# rs232_conn.net
KiCad netlist of a schematic drawn in Altium Designer
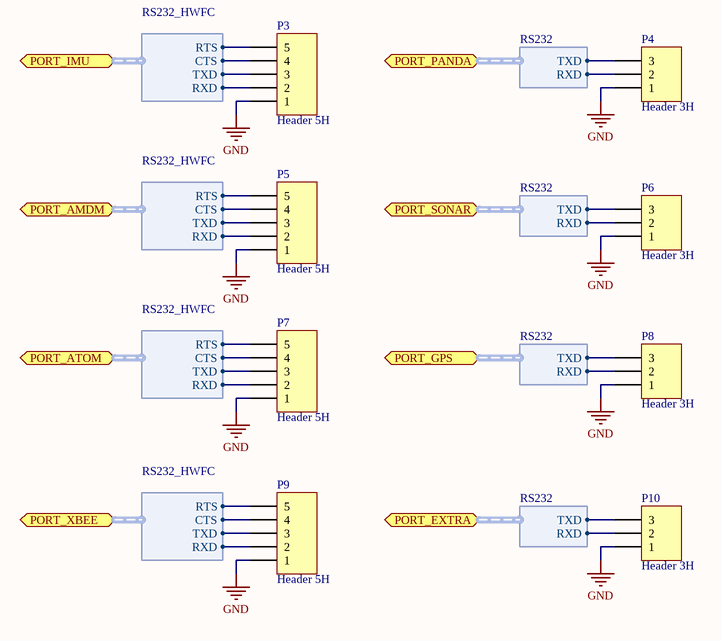
[diagram p0: rs232_conn.SchDoc]

(export (version "E")
  (design (tool "Eeschema 10.0.6"))
  (components
    (comp (ref "P3")
      (value "Header 5H")
      (footprint "S05B-PASK-2")
      (description "Header, 5-Pin, Right Angle")
      (fields (field (name "PUBLISHER") "Altium Limited"))
      (libsource (lib "Miscellaneous Connectors") (part "Header 5H"))
    )
    (comp (ref "P4")
      (value "Header 3H")
      (footprint "S03B-PASK-2")
      (description "Header, 3-Pin, Right Angle")
      (fields (field (name "PUBLISHER") "Altium Limited"))
      (libsource (lib "Miscellaneous Connectors") (part "Header 3H"))
    )
    (comp (ref "P5")
      (value "Header 5H")
      (footprint "S05B-PASK-2")
      (description "Header, 5-Pin, Right Angle")
      (fields (field (name "PUBLISHER") "Altium Limited"))
      (libsource (lib "Miscellaneous Connectors") (part "Header 5H"))
    )
    (comp (ref "P6")
      (value "Header 3H")
      (footprint "S03B-PASK-2")
      (description "Header, 3-Pin, Right Angle")
      (fields (field (name "PUBLISHER") "Altium Limited"))
      (libsource (lib "Miscellaneous Connectors") (part "Header 3H"))
    )
    (comp (ref "P7")
      (value "Header 5H")
      (footprint "S05B-PASK-2")
      (description "Header, 5-Pin, Right Angle")
      (fields (field (name "PUBLISHER") "Altium Limited"))
      (libsource (lib "Miscellaneous Connectors") (part "Header 5H"))
    )
    (comp (ref "P8")
      (value "Header 3H")
      (footprint "S03B-PASK-2")
      (description "Header, 3-Pin, Right Angle")
      (fields (field (name "PUBLISHER") "Altium Limited"))
      (libsource (lib "Miscellaneous Connectors") (part "Header 3H"))
    )
    (comp (ref "P9")
      (value "Header 5H")
      (footprint "S05B-PASK-2")
      (description "Header, 5-Pin, Right Angle")
      (fields (field (name "PUBLISHER") "Altium Limited"))
      (libsource (lib "Miscellaneous Connectors") (part "Header 5H"))
    )
    (comp (ref "P10")
      (value "Header 3H")
      (footprint "S03B-PASK-2")
      (description "Header, 3-Pin, Right Angle")
      (fields (field (name "PUBLISHER") "Altium Limited"))
      (libsource (lib "Miscellaneous Connectors") (part "Header 3H"))
    )
  )
  (nets
    (net (code "5") (name "GND") (class "Default")
      (node (ref "P10") (pin "1") (pinfunction "1_1") (pintype "passive"))
      (node (ref "P3") (pin "1") (pinfunction "1_1") (pintype "passive"))
      (node (ref "P4") (pin "1") (pinfunction "1_1") (pintype "passive"))
      (node (ref "P5") (pin "1") (pinfunction "1_1") (pintype "passive"))
      (node (ref "P6") (pin "1") (pinfunction "1_1") (pintype "passive"))
      (node (ref "P7") (pin "1") (pinfunction "1_1") (pintype "passive"))
      (node (ref "P8") (pin "1") (pinfunction "1_1") (pintype "passive"))
      (node (ref "P9") (pin "1") (pinfunction "1_1") (pintype "passive"))
    )
    (net (code "6") (name "unconnected-(P3-Pad2)") (class "Default")
      (node (ref "P3") (pin "2") (pinfunction "2_2") (pintype "passive"))
    )
    (net (code "7") (name "unconnected-(P3-Pad3)") (class "Default")
      (node (ref "P3") (pin "3") (pinfunction "3_3") (pintype "passive"))
    )
    (net (code "8") (name "unconnected-(P3-Pad4)") (class "Default")
      (node (ref "P3") (pin "4") (pinfunction "4_4") (pintype "passive"))
    )
    (net (code "9") (name "unconnected-(P3-Pad5)") (class "Default")
      (node (ref "P3") (pin "5") (pinfunction "5_5") (pintype "passive"))
    )
    (net (code "10") (name "unconnected-(P4-Pad2)") (class "Default")
      (node (ref "P4") (pin "2") (pinfunction "2_2") (pintype "passive"))
    )
    (net (code "11") (name "unconnected-(P4-Pad3)") (class "Default")
      (node (ref "P4") (pin "3") (pinfunction "3_3") (pintype "passive"))
    )
    (net (code "12") (name "unconnected-(P5-Pad2)") (class "Default")
      (node (ref "P5") (pin "2") (pinfunction "2_2") (pintype "passive"))
    )
    (net (code "13") (name "unconnected-(P5-Pad3)") (class "Default")
      (node (ref "P5") (pin "3") (pinfunction "3_3") (pintype "passive"))
    )
    (net (code "14") (name "unconnected-(P5-Pad4)") (class "Default")
      (node (ref "P5") (pin "4") (pinfunction "4_4") (pintype "passive"))
    )
    (net (code "15") (name "unconnected-(P5-Pad5)") (class "Default")
      (node (ref "P5") (pin "5") (pinfunction "5_5") (pintype "passive"))
    )
    (net (code "16") (name "unconnected-(P6-Pad2)") (class "Default")
      (node (ref "P6") (pin "2") (pinfunction "2_2") (pintype "passive"))
    )
    (net (code "17") (name "unconnected-(P6-Pad3)") (class "Default")
      (node (ref "P6") (pin "3") (pinfunction "3_3") (pintype "passive"))
    )
    (net (code "18") (name "unconnected-(P7-Pad2)") (class "Default")
      (node (ref "P7") (pin "2") (pinfunction "2_2") (pintype "passive"))
    )
    (net (code "19") (name "unconnected-(P7-Pad3)") (class "Default")
      (node (ref "P7") (pin "3") (pinfunction "3_3") (pintype "passive"))
    )
    (net (code "20") (name "unconnected-(P7-Pad4)") (class "Default")
      (node (ref "P7") (pin "4") (pinfunction "4_4") (pintype "passive"))
    )
    (net (code "21") (name "unconnected-(P7-Pad5)") (class "Default")
      (node (ref "P7") (pin "5") (pinfunction "5_5") (pintype "passive"))
    )
    (net (code "22") (name "unconnected-(P8-Pad2)") (class "Default")
      (node (ref "P8") (pin "2") (pinfunction "2_2") (pintype "passive"))
    )
    (net (code "23") (name "unconnected-(P8-Pad3)") (class "Default")
      (node (ref "P8") (pin "3") (pinfunction "3_3") (pintype "passive"))
    )
    (net (code "24") (name "unconnected-(P9-Pad2)") (class "Default")
      (node (ref "P9") (pin "2") (pinfunction "2_2") (pintype "passive"))
    )
    (net (code "25") (name "unconnected-(P9-Pad3)") (class "Default")
      (node (ref "P9") (pin "3") (pinfunction "3_3") (pintype "passive"))
    )
    (net (code "26") (name "unconnected-(P9-Pad4)") (class "Default")
      (node (ref "P9") (pin "4") (pinfunction "4_4") (pintype "passive"))
    )
    (net (code "27") (name "unconnected-(P9-Pad5)") (class "Default")
      (node (ref "P9") (pin "5") (pinfunction "5_5") (pintype "passive"))
    )
    (net (code "28") (name "unconnected-(P10-Pad2)") (class "Default")
      (node (ref "P10") (pin "2") (pinfunction "2_2") (pintype "passive"))
    )
    (net (code "29") (name "unconnected-(P10-Pad3)") (class "Default")
      (node (ref "P10") (pin "3") (pinfunction "3_3") (pintype "passive"))
    )
  )
)
